# dc_link.net
KiCad netlist of a schematic drawn in Altium Designer
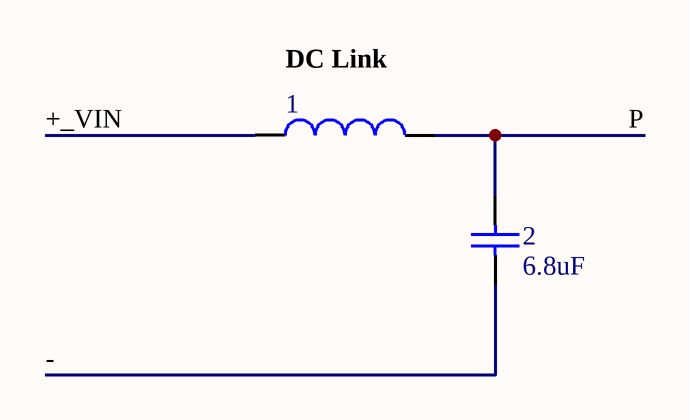
[diagram p0: dc link.SchDoc]

(export (version "E")
  (design (tool "Eeschema 10.0.6"))
  (components
    (comp (ref "1") (value "Inductor") (libsource (lib "Simulation Generic Components") (part "Inductor")))
    (comp (ref "2")
      (value "6.8uF")
      (description "Capacitor")
      (libsource (lib "Simulation Generic Components") (part "Capacitor"))
    )
  )
  (nets
    (net (code "1") (name "/+_VIN") (class "Default")
      (node (ref "1") (pin "1") (pinfunction "1_1") (pintype "passive"))
    )
    (net (code "2") (name "/-") (class "Default")
      (node (ref "2") (pin "1") (pinfunction "1_1") (pintype "passive"))
    )
    (net (code "3") (name "/P") (class "Default")
      (node (ref "1") (pin "2") (pinfunction "2_2") (pintype "passive"))
      (node (ref "2") (pin "2") (pinfunction "2_2") (pintype "passive"))
    )
  )
)
